# 425543_043_3_2.net
KiCad netlist of a schematic drawn in Altium Designer
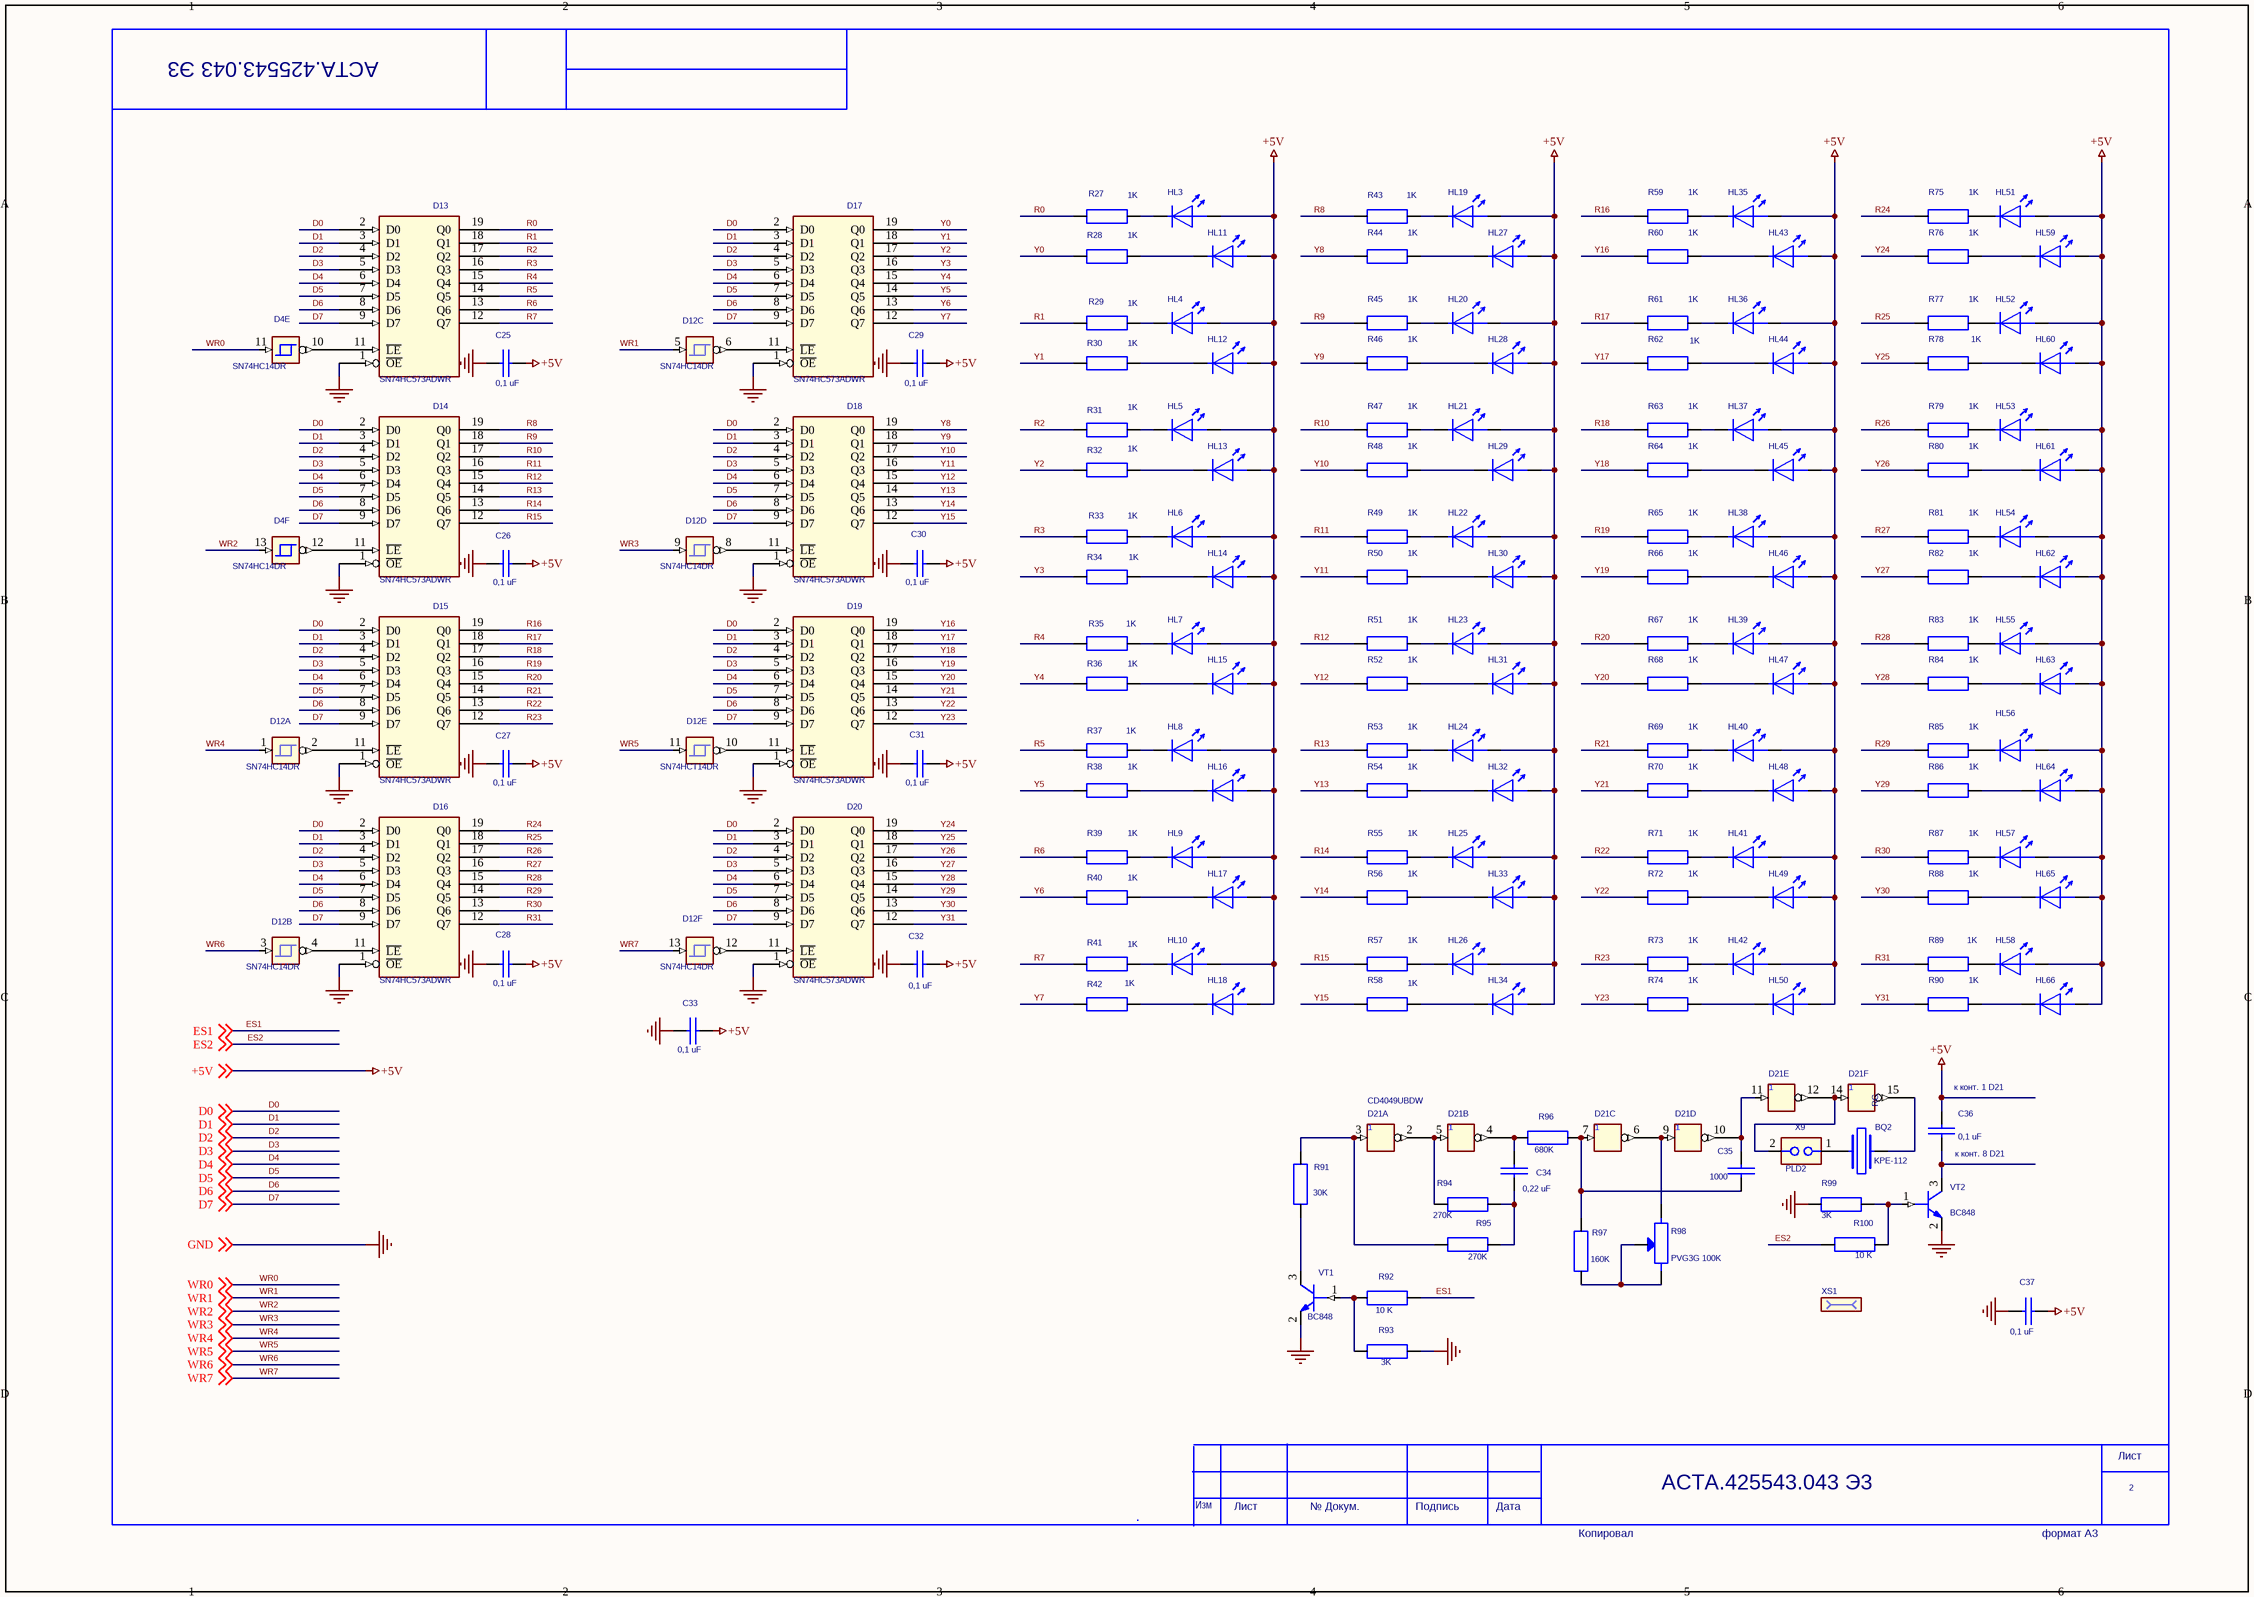
[diagram p0: АСТА.425543.043 Э3 Лист2.SchDoc]

(export (version "E")
  (design (tool "Eeschema 10.0.6"))
  (components
    (comp (ref "BQ2")
      (value "KPE-112")
      (fields (field (name "TYP") "RG"))
      (libsource (lib "*") (part "QUARTZ"))
    )
    (comp (ref "C25") (value "0,1 uF") (footprint "1206.PRT") (libsource (lib "*") (part "CHIP-C")))
    (comp (ref "C26") (value "0,1 uF") (footprint "1206.PRT") (libsource (lib "*") (part "CHIP-C")))
    (comp (ref "C27") (value "0,1 uF") (footprint "1206.PRT") (libsource (lib "*") (part "CHIP-C")))
    (comp (ref "C28") (value "0,1 uF") (footprint "1206.PRT") (libsource (lib "*") (part "CHIP-C")))
    (comp (ref "C29") (value "0,1 uF") (footprint "1206.PRT") (libsource (lib "*") (part "CHIP-C")))
    (comp (ref "C30") (value "0,1 uF") (footprint "1206.PRT") (libsource (lib "*") (part "CHIP-C")))
    (comp (ref "C31") (value "0,1 uF") (footprint "1206.PRT") (libsource (lib "*") (part "CHIP-C")))
    (comp (ref "C32") (value "0,1 uF") (footprint "1206.PRT") (libsource (lib "*") (part "CHIP-C")))
    (comp (ref "C33") (value "0,1 uF") (footprint "1206.PRT") (libsource (lib "*") (part "CHIP-C")))
    (comp (ref "C34") (value "0,22 uF") (footprint "1206.PRT") (libsource (lib "*") (part "CHIP-C")))
    (comp (ref "C35") (value "1000") (footprint "1206.PRT") (libsource (lib "*") (part "CHIP-C")))
    (comp (ref "C36") (value "0,1 uF") (footprint "1206.PRT") (libsource (lib "*") (part "CHIP-C")))
    (comp (ref "C37") (value "0,1 uF") (footprint "1206.PRT") (libsource (lib "*") (part "CHIP-C")))
    (comp (ref "D4") (value "SN74HC14DR") (libsource (lib "*") (part "14069_5")))
    (comp (ref "D12") (value "SN74HC14DR") (libsource (lib "*") (part "74HC14_1")))
    (comp (ref "D13") (value "SN74HC573ADWR") (libsource (lib "*") (part "74HC573_0")))
    (comp (ref "D14") (value "SN74HC573ADWR") (libsource (lib "*") (part "74HC573_5")))
    (comp (ref "D15") (value "SN74HC573ADWR") (libsource (lib "*") (part "74HC573_0")))
    (comp (ref "D16") (value "SN74HC573ADWR") (libsource (lib "*") (part "74HC573_0")))
    (comp (ref "D17") (value "SN74HC573ADWR") (libsource (lib "*") (part "74HC573_6")))
    (comp (ref "D18") (value "SN74HC573ADWR") (libsource (lib "*") (part "74HC573_0")))
    (comp (ref "D19") (value "SN74HC573ADWR") (libsource (lib "*") (part "74HC573_0")))
    (comp (ref "D20") (value "SN74HC573ADWR") (libsource (lib "*") (part "74HC573_0")))
    (comp (ref "D21") (value "CD4049UBDW") (libsource (lib "*") (part "4049_0")))
    (comp (ref "HL3") (value "L-934ID-5V") (libsource (lib "*") (part "AL307AM")))
    (comp (ref "HL4") (value "L-934ID-5V") (libsource (lib "*") (part "AL307AM")))
    (comp (ref "HL5") (value "L-934ID-5V") (libsource (lib "*") (part "AL307AM")))
    (comp (ref "HL6") (value "L-934ID-5V") (libsource (lib "*") (part "AL307AM")))
    (comp (ref "HL7") (value "L-934ID-5V") (libsource (lib "*") (part "AL307AM")))
    (comp (ref "HL8") (value "L-934ID-5V") (libsource (lib "*") (part "AL307AM")))
    (comp (ref "HL9") (value "L-934ID-5V") (libsource (lib "*") (part "AL307AM")))
    (comp (ref "HL10") (value "L-934ID-5V") (libsource (lib "*") (part "AL307AM")))
    (comp (ref "HL11") (value "L-934YD-5V") (libsource (lib "*") (part "AL307AM")))
    (comp (ref "HL12") (value "L-934YD-5V") (libsource (lib "*") (part "AL307AM")))
    (comp (ref "HL13") (value "L-934YD-5V") (libsource (lib "*") (part "AL307AM")))
    (comp (ref "HL14") (value "L-934YD-5V") (libsource (lib "*") (part "AL307AM")))
    (comp (ref "HL15") (value "L-934YD-5V") (libsource (lib "*") (part "AL307AM")))
    (comp (ref "HL16") (value "L-934YD-5V") (libsource (lib "*") (part "AL307AM")))
    (comp (ref "HL17") (value "L-934YD-5V") (libsource (lib "*") (part "AL307AM")))
    (comp (ref "HL18") (value "L-934YD-5V") (libsource (lib "*") (part "AL307AM")))
    (comp (ref "HL19") (value "L-934ID-5V") (libsource (lib "*") (part "AL307AM")))
    (comp (ref "HL20") (value "L-934ID-5V") (libsource (lib "*") (part "AL307AM")))
    (comp (ref "HL21") (value "L-934ID-5V") (libsource (lib "*") (part "AL307AM")))
    (comp (ref "HL22") (value "L-934ID-5V") (libsource (lib "*") (part "AL307AM")))
    (comp (ref "HL23") (value "L-934ID-5V") (libsource (lib "*") (part "AL307AM")))
    (comp (ref "HL24") (value "L-934ID-5V") (libsource (lib "*") (part "AL307AM")))
    (comp (ref "HL25") (value "L-934ID-5V") (libsource (lib "*") (part "AL307AM")))
    (comp (ref "HL26") (value "L-934ID-5V") (libsource (lib "*") (part "AL307AM")))
    (comp (ref "HL27") (value "L-934YD-5V") (libsource (lib "*") (part "AL307AM")))
    (comp (ref "HL28") (value "L-934YD-5V") (libsource (lib "*") (part "AL307AM")))
    (comp (ref "HL29") (value "L-934YD-5V") (libsource (lib "*") (part "AL307AM")))
    (comp (ref "HL30") (value "L-934YD-5V") (libsource (lib "*") (part "AL307AM")))
    (comp (ref "HL31") (value "L-934YD-5V") (libsource (lib "*") (part "AL307AM")))
    (comp (ref "HL32") (value "L-934YD-5V") (libsource (lib "*") (part "AL307AM")))
    (comp (ref "HL33") (value "L-934YD-5V") (libsource (lib "*") (part "AL307AM")))
    (comp (ref "HL34") (value "L-934YD-5V") (libsource (lib "*") (part "AL307AM")))
    (comp (ref "HL35") (value "L-934ID-5V") (libsource (lib "*") (part "AL307AM")))
    (comp (ref "HL36") (value "L-934ID-5V") (libsource (lib "*") (part "AL307AM")))
    (comp (ref "HL37") (value "L-934ID-5V") (libsource (lib "*") (part "AL307AM")))
    (comp (ref "HL38") (value "L-934ID-5V") (libsource (lib "*") (part "AL307AM")))
    (comp (ref "HL39") (value "L-934ID-5V") (libsource (lib "*") (part "AL307AM")))
    (comp (ref "HL40") (value "L-934ID-5V") (libsource (lib "*") (part "AL307AM")))
    (comp (ref "HL41") (value "L-934ID-5V") (libsource (lib "*") (part "AL307AM")))
    (comp (ref "HL42") (value "L-934ID-5V") (libsource (lib "*") (part "AL307AM")))
    (comp (ref "HL43") (value "L-934YD-5V") (libsource (lib "*") (part "AL307AM")))
    (comp (ref "HL44") (value "L-934YD-5V") (libsource (lib "*") (part "AL307AM")))
    (comp (ref "HL45") (value "L-934YD-5V") (libsource (lib "*") (part "AL307AM")))
    (comp (ref "HL46") (value "L-934YD-5V") (libsource (lib "*") (part "AL307AM")))
    (comp (ref "HL47") (value "L-934YD-5V") (libsource (lib "*") (part "AL307AM")))
    (comp (ref "HL48") (value "L-934YD-5V") (libsource (lib "*") (part "AL307AM")))
    (comp (ref "HL49") (value "L-934YD-5V") (libsource (lib "*") (part "AL307AM")))
    (comp (ref "HL50") (value "L-934YD-5V") (libsource (lib "*") (part "AL307AM")))
    (comp (ref "HL51") (value "L-934ID-5V") (libsource (lib "*") (part "AL307AM")))
    (comp (ref "HL52") (value "L-934YD-5V") (libsource (lib "*") (part "AL307AM")))
    (comp (ref "HL53") (value "L-934ID-5V") (libsource (lib "*") (part "AL307AM")))
    (comp (ref "HL54") (value "L-934ID-5V") (libsource (lib "*") (part "AL307AM")))
    (comp (ref "HL55") (value "L-934ID-5V") (libsource (lib "*") (part "AL307AM")))
    (comp (ref "HL56") (value "L-934ID-5V") (libsource (lib "*") (part "AL307AM")))
    (comp (ref "HL57") (value "L-934ID-5V") (libsource (lib "*") (part "AL307AM")))
    (comp (ref "HL58") (value "L-934ID-5V") (libsource (lib "*") (part "AL307AM")))
    (comp (ref "HL59") (value "L-934ID-5V") (libsource (lib "*") (part "AL307AM")))
    (comp (ref "HL60") (value "L-934YD-5V") (libsource (lib "*") (part "AL307AM")))
    (comp (ref "HL61") (value "L-934YD-5V") (libsource (lib "*") (part "AL307AM")))
    (comp (ref "HL62") (value "L-934YD-5V") (libsource (lib "*") (part "AL307AM")))
    (comp (ref "HL63") (value "L-934YD-5V") (libsource (lib "*") (part "AL307AM")))
    (comp (ref "HL64") (value "L-934YD-5V") (libsource (lib "*") (part "AL307AM")))
    (comp (ref "HL65") (value "L-934YD-5V") (libsource (lib "*") (part "AL307AM")))
    (comp (ref "HL66") (value "L-934YD-5V") (libsource (lib "*") (part "AL307AM")))
    (comp (ref "R27") (value "1K") (footprint "1206.PRT") (libsource (lib "*") (part "CHIP-R")))
    (comp (ref "R28") (value "1K") (footprint "1206.PRT") (libsource (lib "*") (part "CHIP-R")))
    (comp (ref "R29") (value "1K") (footprint "1206.PRT") (libsource (lib "*") (part "CHIP-R")))
    (comp (ref "R30") (value "1K") (footprint "1206.PRT") (libsource (lib "*") (part "CHIP-R")))
    (comp (ref "R31") (value "1K") (footprint "1206.PRT") (libsource (lib "*") (part "CHIP-R")))
    (comp (ref "R32") (value "1K") (footprint "1206.PRT") (libsource (lib "*") (part "CHIP-R")))
    (comp (ref "R33") (value "1K") (footprint "1206.PRT") (libsource (lib "*") (part "CHIP-R")))
    (comp (ref "R34") (value "1K") (footprint "1206.PRT") (libsource (lib "*") (part "CHIP-R")))
    (comp (ref "R35") (value "1K") (footprint "1206.PRT") (libsource (lib "*") (part "CHIP-R")))
    (comp (ref "R36") (value "1K") (footprint "1206.PRT") (libsource (lib "*") (part "CHIP-R")))
    (comp (ref "R37") (value "1K") (footprint "1206.PRT") (libsource (lib "*") (part "CHIP-R")))
    (comp (ref "R38") (value "1K") (footprint "1206.PRT") (libsource (lib "*") (part "CHIP-R")))
    (comp (ref "R39") (value "1K") (footprint "1206.PRT") (libsource (lib "*") (part "CHIP-R")))
    (comp (ref "R40") (value "1K") (footprint "1206.PRT") (libsource (lib "*") (part "CHIP-R")))
    (comp (ref "R41") (value "1K") (footprint "1206.PRT") (libsource (lib "*") (part "CHIP-R")))
    (comp (ref "R42") (value "1K") (footprint "1206.PRT") (libsource (lib "*") (part "CHIP-R")))
    (comp (ref "R43") (value "1K") (footprint "1206.PRT") (libsource (lib "*") (part "CHIP-R")))
    (comp (ref "R44") (value "1K") (footprint "1206.PRT") (libsource (lib "*") (part "CHIP-R")))
    (comp (ref "R45") (value "1K") (footprint "1206.PRT") (libsource (lib "*") (part "CHIP-R")))
    (comp (ref "R46") (value "1K") (footprint "1206.PRT") (libsource (lib "*") (part "CHIP-R")))
    (comp (ref "R47") (value "1K") (footprint "1206.PRT") (libsource (lib "*") (part "CHIP-R")))
    (comp (ref "R48") (value "1K") (footprint "1206.PRT") (libsource (lib "*") (part "CHIP-R")))
    (comp (ref "R49") (value "1K") (footprint "1206.PRT") (libsource (lib "*") (part "CHIP-R")))
    (comp (ref "R50") (value "1K") (footprint "1206.PRT") (libsource (lib "*") (part "CHIP-R")))
    (comp (ref "R51") (value "1K") (footprint "1206.PRT") (libsource (lib "*") (part "CHIP-R")))
    (comp (ref "R52") (value "1K") (footprint "1206.PRT") (libsource (lib "*") (part "CHIP-R")))
    (comp (ref "R53") (value "1K") (footprint "1206.PRT") (libsource (lib "*") (part "CHIP-R")))
    (comp (ref "R54") (value "1K") (footprint "1206.PRT") (libsource (lib "*") (part "CHIP-R")))
    (comp (ref "R55") (value "1K") (footprint "1206.PRT") (libsource (lib "*") (part "CHIP-R")))
    (comp (ref "R56") (value "1K") (footprint "1206.PRT") (libsource (lib "*") (part "CHIP-R")))
    (comp (ref "R57") (value "1K") (footprint "1206.PRT") (libsource (lib "*") (part "CHIP-R")))
    (comp (ref "R58") (value "1K") (footprint "1206.PRT") (libsource (lib "*") (part "CHIP-R")))
    (comp (ref "R59") (value "1K") (footprint "1206.PRT") (libsource (lib "*") (part "CHIP-R")))
    (comp (ref "R60") (value "1K") (footprint "1206.PRT") (libsource (lib "*") (part "CHIP-R")))
    (comp (ref "R61") (value "1K") (footprint "1206.PRT") (libsource (lib "*") (part "CHIP-R")))
    (comp (ref "R62") (value "1K") (footprint "1206.PRT") (libsource (lib "*") (part "CHIP-R")))
    (comp (ref "R63") (value "1K") (footprint "1206.PRT") (libsource (lib "*") (part "CHIP-R")))
    (comp (ref "R64") (value "1K") (footprint "1206.PRT") (libsource (lib "*") (part "CHIP-R")))
    (comp (ref "R65") (value "1K") (footprint "1206.PRT") (libsource (lib "*") (part "CHIP-R")))
    (comp (ref "R66") (value "1K") (footprint "1206.PRT") (libsource (lib "*") (part "CHIP-R")))
    (comp (ref "R67") (value "1K") (footprint "1206.PRT") (libsource (lib "*") (part "CHIP-R")))
    (comp (ref "R68") (value "1K") (footprint "1206.PRT") (libsource (lib "*") (part "CHIP-R")))
    (comp (ref "R69") (value "1K") (footprint "1206.PRT") (libsource (lib "*") (part "CHIP-R")))
    (comp (ref "R70") (value "1K") (footprint "1206.PRT") (libsource (lib "*") (part "CHIP-R")))
    (comp (ref "R71") (value "1K") (footprint "1206.PRT") (libsource (lib "*") (part "CHIP-R")))
    (comp (ref "R72") (value "1K") (footprint "1206.PRT") (libsource (lib "*") (part "CHIP-R")))
    (comp (ref "R73") (value "1K") (footprint "1206.PRT") (libsource (lib "*") (part "CHIP-R")))
    (comp (ref "R74") (value "1K") (footprint "1206.PRT") (libsource (lib "*") (part "CHIP-R")))
    (comp (ref "R75") (value "1K") (footprint "1206.PRT") (libsource (lib "*") (part "CHIP-R")))
    (comp (ref "R76") (value "1K") (footprint "1206.PRT") (libsource (lib "*") (part "CHIP-R")))
    (comp (ref "R77") (value "1K") (footprint "1206.PRT") (libsource (lib "*") (part "CHIP-R")))
    (comp (ref "R78") (value "1K") (footprint "1206.PRT") (libsource (lib "*") (part "CHIP-R")))
    (comp (ref "R79") (value "1K") (footprint "1206.PRT") (libsource (lib "*") (part "CHIP-R")))
    (comp (ref "R80") (value "1K") (footprint "1206.PRT") (libsource (lib "*") (part "CHIP-R")))
    (comp (ref "R81") (value "1K") (footprint "1206.PRT") (libsource (lib "*") (part "CHIP-R")))
    (comp (ref "R82") (value "1K") (footprint "1206.PRT") (libsource (lib "*") (part "CHIP-R")))
    (comp (ref "R83") (value "1K") (footprint "1206.PRT") (libsource (lib "*") (part "CHIP-R")))
    (comp (ref "R84") (value "1K") (footprint "1206.PRT") (libsource (lib "*") (part "CHIP-R")))
    (comp (ref "R85") (value "1K") (footprint "1206.PRT") (libsource (lib "*") (part "CHIP-R")))
    (comp (ref "R86") (value "1K") (footprint "1206.PRT") (libsource (lib "*") (part "CHIP-R")))
    (comp (ref "R87") (value "1K") (footprint "1206.PRT") (libsource (lib "*") (part "CHIP-R")))
    (comp (ref "R88") (value "1K") (footprint "1206.PRT") (libsource (lib "*") (part "CHIP-R")))
    (comp (ref "R89") (value "1K") (footprint "1206.PRT") (libsource (lib "*") (part "CHIP-R")))
    (comp (ref "R90") (value "1K") (footprint "1206.PRT") (libsource (lib "*") (part "CHIP-R")))
    (comp (ref "R91") (value "30K") (footprint "1206.PRT") (libsource (lib "*") (part "CHIP-R")))
    (comp (ref "R92") (value "10 K") (footprint "1206.PRT") (libsource (lib "*") (part "CHIP-R")))
    (comp (ref "R93") (value "3K") (footprint "1206.PRT") (libsource (lib "*") (part "CHIP-R")))
    (comp (ref "R94") (value "270K") (footprint "1206.PRT") (libsource (lib "*") (part "CHIP-R")))
    (comp (ref "R95") (value "270K") (footprint "1206.PRT") (libsource (lib "*") (part "CHIP-R")))
    (comp (ref "R96") (value "680K") (footprint "1206.PRT") (libsource (lib "*") (part "CHIP-R")))
    (comp (ref "R97") (value "160K") (footprint "1206.PRT") (libsource (lib "*") (part "CHIP-R")))
    (comp (ref "R98") (value "PVG3G 100K") (libsource (lib "*") (part "RESISTOR VAR_1")))
    (comp (ref "R99") (value "3K") (footprint "1206.PRT") (libsource (lib "*") (part "CHIP-R")))
    (comp (ref "R100") (value "10 K") (footprint "1206.PRT") (libsource (lib "*") (part "CHIP-R")))
    (comp (ref "VT1") (value "BC848") (libsource (lib "*") (part "NPN CBE_0")))
    (comp (ref "VT2") (value "BC848") (libsource (lib "*") (part "NPN CBE_0")))
    (comp (ref "X9") (value "PLD2") (libsource (lib "*") (part "EXTEND_22_Dup1")))
    (comp (ref "XS1") (value "EXTEND_11") (libsource (lib "АСТА.425543.043 Э3_Library") (part "EXTEND_11")))
  )
  (nets
    (net (code "1") (name "+5V") (class "Default")
      (node (ref "C25") (pin "2") (pinfunction "2_2") (pintype "passive"))
      (node (ref "C26") (pin "2") (pinfunction "2_2") (pintype "passive"))
      (node (ref "C27") (pin "2") (pinfunction "2_2") (pintype "passive"))
      (node (ref "C28") (pin "2") (pinfunction "2_2") (pintype "passive"))
      (node (ref "C29") (pin "2") (pinfunction "2_2") (pintype "passive"))
      (node (ref "C30") (pin "2") (pinfunction "2_2") (pintype "passive"))
      (node (ref "C31") (pin "2") (pinfunction "2_2") (pintype "passive"))
      (node (ref "C32") (pin "2") (pinfunction "2_2") (pintype "passive"))
      (node (ref "C33") (pin "2") (pinfunction "2_2") (pintype "passive"))
      (node (ref "C36") (pin "2") (pinfunction "2_2") (pintype "passive"))
      (node (ref "C37") (pin "2") (pinfunction "2_2") (pintype "passive"))
      (node (ref "HL10") (pin "1") (pinfunction "ANODE_1") (pintype "passive"))
      (node (ref "HL11") (pin "1") (pinfunction "ANODE_1") (pintype "passive"))
      (node (ref "HL12") (pin "1") (pinfunction "ANODE_1") (pintype "passive"))
      (node (ref "HL13") (pin "1") (pinfunction "ANODE_1") (pintype "passive"))
      (node (ref "HL14") (pin "1") (pinfunction "ANODE_1") (pintype "passive"))
      (node (ref "HL15") (pin "1") (pinfunction "ANODE_1") (pintype "passive"))
      (node (ref "HL16") (pin "1") (pinfunction "ANODE_1") (pintype "passive"))
      (node (ref "HL17") (pin "1") (pinfunction "ANODE_1") (pintype "passive"))
      (node (ref "HL18") (pin "1") (pinfunction "ANODE_1") (pintype "passive"))
      (node (ref "HL19") (pin "1") (pinfunction "ANODE_1") (pintype "passive"))
      (node (ref "HL20") (pin "1") (pinfunction "ANODE_1") (pintype "passive"))
      (node (ref "HL21") (pin "1") (pinfunction "ANODE_1") (pintype "passive"))
      (node (ref "HL22") (pin "1") (pinfunction "ANODE_1") (pintype "passive"))
      (node (ref "HL23") (pin "1") (pinfunction "ANODE_1") (pintype "passive"))
      (node (ref "HL24") (pin "1") (pinfunction "ANODE_1") (pintype "passive"))
      (node (ref "HL25") (pin "1") (pinfunction "ANODE_1") (pintype "passive"))
      (node (ref "HL26") (pin "1") (pinfunction "ANODE_1") (pintype "passive"))
      (node (ref "HL27") (pin "1") (pinfunction "ANODE_1") (pintype "passive"))
      (node (ref "HL28") (pin "1") (pinfunction "ANODE_1") (pintype "passive"))
      (node (ref "HL29") (pin "1") (pinfunction "ANODE_1") (pintype "passive"))
      (node (ref "HL3") (pin "1") (pinfunction "ANODE_1") (pintype "passive"))
      (node (ref "HL30") (pin "1") (pinfunction "ANODE_1") (pintype "passive"))
      (node (ref "HL31") (pin "1") (pinfunction "ANODE_1") (pintype "passive"))
      (node (ref "HL32") (pin "1") (pinfunction "ANODE_1") (pintype "passive"))
      (node (ref "HL33") (pin "1") (pinfunction "ANODE_1") (pintype "passive"))
      (node (ref "HL34") (pin "1") (pinfunction "ANODE_1") (pintype "passive"))
      (node (ref "HL35") (pin "1") (pinfunction "ANODE_1") (pintype "passive"))
      (node (ref "HL36") (pin "1") (pinfunction "ANODE_1") (pintype "passive"))
      (node (ref "HL37") (pin "1") (pinfunction "ANODE_1") (pintype "passive"))
      (node (ref "HL38") (pin "1") (pinfunction "ANODE_1") (pintype "passive"))
      (node (ref "HL39") (pin "1") (pinfunction "ANODE_1") (pintype "passive"))
      (node (ref "HL4") (pin "1") (pinfunction "ANODE_1") (pintype "passive"))
      (node (ref "HL40") (pin "1") (pinfunction "ANODE_1") (pintype "passive"))
      (node (ref "HL41") (pin "1") (pinfunction "ANODE_1") (pintype "passive"))
      (node (ref "HL42") (pin "1") (pinfunction "ANODE_1") (pintype "passive"))
      (node (ref "HL43") (pin "1") (pinfunction "ANODE_1") (pintype "passive"))
      (node (ref "HL44") (pin "1") (pinfunction "ANODE_1") (pintype "passive"))
      (node (ref "HL45") (pin "1") (pinfunction "ANODE_1") (pintype "passive"))
      (node (ref "HL46") (pin "1") (pinfunction "ANODE_1") (pintype "passive"))
      (node (ref "HL47") (pin "1") (pinfunction "ANODE_1") (pintype "passive"))
      (node (ref "HL48") (pin "1") (pinfunction "ANODE_1") (pintype "passive"))
      (node (ref "HL49") (pin "1") (pinfunction "ANODE_1") (pintype "passive"))
      (node (ref "HL5") (pin "1") (pinfunction "ANODE_1") (pintype "passive"))
      (node (ref "HL50") (pin "1") (pinfunction "ANODE_1") (pintype "passive"))
      (node (ref "HL51") (pin "1") (pinfunction "ANODE_1") (pintype "passive"))
      (node (ref "HL52") (pin "1") (pinfunction "ANODE_1") (pintype "passive"))
      (node (ref "HL53") (pin "1") (pinfunction "ANODE_1") (pintype "passive"))
      (node (ref "HL54") (pin "1") (pinfunction "ANODE_1") (pintype "passive"))
      (node (ref "HL55") (pin "1") (pinfunction "ANODE_1") (pintype "passive"))
      (node (ref "HL56") (pin "1") (pinfunction "ANODE_1") (pintype "passive"))
      (node (ref "HL57") (pin "1") (pinfunction "ANODE_1") (pintype "passive"))
      (node (ref "HL58") (pin "1") (pinfunction "ANODE_1") (pintype "passive"))
      (node (ref "HL59") (pin "1") (pinfunction "ANODE_1") (pintype "passive"))
      (node (ref "HL6") (pin "1") (pinfunction "ANODE_1") (pintype "passive"))
      (node (ref "HL60") (pin "1") (pinfunction "ANODE_1") (pintype "passive"))
      (node (ref "HL61") (pin "1") (pinfunction "ANODE_1") (pintype "passive"))
      (node (ref "HL62") (pin "1") (pinfunction "ANODE_1") (pintype "passive"))
      (node (ref "HL63") (pin "1") (pinfunction "ANODE_1") (pintype "passive"))
      (node (ref "HL64") (pin "1") (pinfunction "ANODE_1") (pintype "passive"))
      (node (ref "HL65") (pin "1") (pinfunction "ANODE_1") (pintype "passive"))
      (node (ref "HL66") (pin "1") (pinfunction "ANODE_1") (pintype "passive"))
      (node (ref "HL7") (pin "1") (pinfunction "ANODE_1") (pintype "passive"))
      (node (ref "HL8") (pin "1") (pinfunction "ANODE_1") (pintype "passive"))
      (node (ref "HL9") (pin "1") (pinfunction "ANODE_1") (pintype "passive"))
    )
    (net (code "2") (name "/R0") (class "Default")
      (node (ref "D13") (pin "19") (pinfunction "Q0_19") (pintype "tri_state"))
      (node (ref "R27") (pin "1") (pinfunction "1_1") (pintype "passive"))
    )
    (net (code "3") (name "/R1") (class "Default")
      (node (ref "D13") (pin "18") (pinfunction "Q1_18") (pintype "tri_state"))
      (node (ref "R29") (pin "1") (pinfunction "1_1") (pintype "passive"))
    )
    (net (code "4") (name "/R2") (class "Default")
      (node (ref "D13") (pin "17") (pinfunction "Q2_17") (pintype "tri_state"))
      (node (ref "R31") (pin "1") (pinfunction "1_1") (pintype "passive"))
    )
    (net (code "5") (name "/R3") (class "Default")
      (node (ref "D13") (pin "16") (pinfunction "Q3_16") (pintype "tri_state"))
      (node (ref "R33") (pin "1") (pinfunction "1_1") (pintype "passive"))
    )
    (net (code "6") (name "/R4") (class "Default")
      (node (ref "D13") (pin "15") (pinfunction "Q4_15") (pintype "tri_state"))
      (node (ref "R35") (pin "1") (pinfunction "1_1") (pintype "passive"))
    )
    (net (code "7") (name "/R5") (class "Default")
      (node (ref "D13") (pin "14") (pinfunction "Q5_14") (pintype "tri_state"))
      (node (ref "R37") (pin "1") (pinfunction "1_1") (pintype "passive"))
    )
    (net (code "8") (name "/R6") (class "Default")
      (node (ref "D13") (pin "13") (pinfunction "Q6_13") (pintype "tri_state"))
      (node (ref "R39") (pin "1") (pinfunction "1_1") (pintype "passive"))
    )
    (net (code "9") (name "/R7") (class "Default")
      (node (ref "D13") (pin "12") (pinfunction "Q7_12") (pintype "tri_state"))
      (node (ref "R41") (pin "1") (pinfunction "1_1") (pintype "passive"))
    )
    (net (code "10") (name "/R8") (class "Default")
      (node (ref "D14") (pin "19") (pinfunction "Q0_19") (pintype "tri_state"))
      (node (ref "R43") (pin "1") (pinfunction "1_1") (pintype "passive"))
    )
    (net (code "11") (name "/R9") (class "Default")
      (node (ref "D14") (pin "18") (pinfunction "Q1_18") (pintype "tri_state"))
      (node (ref "R45") (pin "1") (pinfunction "1_1") (pintype "passive"))
    )
    (net (code "12") (name "/R10") (class "Default")
      (node (ref "D14") (pin "17") (pinfunction "Q2_17") (pintype "tri_state"))
      (node (ref "R47") (pin "1") (pinfunction "1_1") (pintype "passive"))
    )
    (net (code "13") (name "/R11") (class "Default")
      (node (ref "D14") (pin "16") (pinfunction "Q3_16") (pintype "tri_state"))
      (node (ref "R49") (pin "1") (pinfunction "1_1") (pintype "passive"))
    )
    (net (code "14") (name "/R12") (class "Default")
      (node (ref "D14") (pin "15") (pinfunction "Q4_15") (pintype "tri_state"))
      (node (ref "R51") (pin "1") (pinfunction "1_1") (pintype "passive"))
    )
    (net (code "15") (name "/R13") (class "Default")
      (node (ref "D14") (pin "14") (pinfunction "Q5_14") (pintype "tri_state"))
      (node (ref "R53") (pin "1") (pinfunction "1_1") (pintype "passive"))
    )
    (net (code "16") (name "/R14") (class "Default")
      (node (ref "D14") (pin "13") (pinfunction "Q6_13") (pintype "tri_state"))
      (node (ref "R55") (pin "1") (pinfunction "1_1") (pintype "passive"))
    )
    (net (code "17") (name "/R15") (class "Default")
      (node (ref "D14") (pin "12") (pinfunction "Q7_12") (pintype "tri_state"))
      (node (ref "R57") (pin "1") (pinfunction "1_1") (pintype "passive"))
    )
    (net (code "18") (name "/R16") (class "Default")
      (node (ref "D15") (pin "19") (pinfunction "Q0_19") (pintype "tri_state"))
      (node (ref "R59") (pin "1") (pinfunction "1_1") (pintype "passive"))
    )
    (net (code "19") (name "/R17") (class "Default")
      (node (ref "D15") (pin "18") (pinfunction "Q1_18") (pintype "tri_state"))
      (node (ref "R61") (pin "1") (pinfunction "1_1") (pintype "passive"))
    )
    (net (code "20") (name "/R18") (class "Default")
      (node (ref "D15") (pin "17") (pinfunction "Q2_17") (pintype "tri_state"))
      (node (ref "R63") (pin "1") (pinfunction "1_1") (pintype "passive"))
    )
    (net (code "21") (name "/R19") (class "Default")
      (node (ref "D15") (pin "16") (pinfunction "Q3_16") (pintype "tri_state"))
      (node (ref "R65") (pin "1") (pinfunction "1_1") (pintype "passive"))
    )
    (net (code "22") (name "/R20") (class "Default")
      (node (ref "D15") (pin "15") (pinfunction "Q4_15") (pintype "tri_state"))
      (node (ref "R67") (pin "1") (pinfunction "1_1") (pintype "passive"))
    )
    (net (code "23") (name "/R21") (class "Default")
      (node (ref "D15") (pin "14") (pinfunction "Q5_14") (pintype "tri_state"))
      (node (ref "R69") (pin "1") (pinfunction "1_1") (pintype "passive"))
    )
    (net (code "24") (name "/R22") (class "Default")
      (node (ref "D15") (pin "13") (pinfunction "Q6_13") (pintype "tri_state"))
      (node (ref "R71") (pin "1") (pinfunction "1_1") (pintype "passive"))
    )
    (net (code "25") (name "/R23") (class "Default")
      (node (ref "D15") (pin "12") (pinfunction "Q7_12") (pintype "tri_state"))
      (node (ref "R73") (pin "1") (pinfunction "1_1") (pintype "passive"))
    )
    (net (code "26") (name "/R24") (class "Default")
      (node (ref "D16") (pin "19") (pinfunction "Q0_19") (pintype "tri_state"))
      (node (ref "R75") (pin "1") (pinfunction "1_1") (pintype "passive"))
    )
    (net (code "27") (name "/R25") (class "Default")
      (node (ref "D16") (pin "18") (pinfunction "Q1_18") (pintype "tri_state"))
      (node (ref "R77") (pin "1") (pinfunction "1_1") (pintype "passive"))
    )
    (net (code "28") (name "/R26") (class "Default")
      (node (ref "D16") (pin "17") (pinfunction "Q2_17") (pintype "tri_state"))
      (node (ref "R79") (pin "1") (pinfunction "1_1") (pintype "passive"))
    )
    (net (code "29") (name "/R27") (class "Default")
      (node (ref "D16") (pin "16") (pinfunction "Q3_16") (pintype "tri_state"))
      (node (ref "R81") (pin "1") (pinfunction "1_1") (pintype "passive"))
    )
    (net (code "30") (name "/R28") (class "Default")
      (node (ref "D16") (pin "15") (pinfunction "Q4_15") (pintype "tri_state"))
      (node (ref "R83") (pin "1") (pinfunction "1_1") (pintype "passive"))
    )
    (net (code "31") (name "/R29") (class "Default")
      (node (ref "D16") (pin "14") (pinfunction "Q5_14") (pintype "tri_state"))
      (node (ref "R85") (pin "1") (pinfunction "1_1") (pintype "passive"))
    )
    (net (code "32") (name "/R30") (class "Default")
      (node (ref "D16") (pin "13") (pinfunction "Q6_13") (pintype "tri_state"))
      (node (ref "R87") (pin "1") (pinfunction "1_1") (pintype "passive"))
    )
    (net (code "33") (name "/R31") (class "Default")
      (node (ref "D16") (pin "12") (pinfunction "Q7_12") (pintype "tri_state"))
      (node (ref "R89") (pin "1") (pinfunction "1_1") (pintype "passive"))
    )
    (net (code "34") (name "/Y0") (class "Default")
      (node (ref "D17") (pin "19") (pinfunction "Q0_19") (pintype "tri_state"))
      (node (ref "R28") (pin "1") (pinfunction "1_1") (pintype "passive"))
    )
    (net (code "35") (name "/Y1") (class "Default")
      (node (ref "D17") (pin "18") (pinfunction "Q1_18") (pintype "tri_state"))
      (node (ref "R30") (pin "1") (pinfunction "1_1") (pintype "passive"))
    )
    (net (code "36") (name "/Y2") (class "Default")
      (node (ref "D17") (pin "17") (pinfunction "Q2_17") (pintype "tri_state"))
      (node (ref "R32") (pin "1") (pinfunction "1_1") (pintype "passive"))
    )
    (net (code "37") (name "/Y3") (class "Default")
      (node (ref "D17") (pin "16") (pinfunction "Q3_16") (pintype "tri_state"))
      (node (ref "R34") (pin "1") (pinfunction "1_1") (pintype "passive"))
    )
    (net (code "38") (name "/Y4") (class "Default")
      (node (ref "D17") (pin "15") (pinfunction "Q4_15") (pintype "tri_state"))
      (node (ref "R36") (pin "1") (pinfunction "1_1") (pintype "passive"))
    )
    (net (code "39") (name "/Y5") (class "Default")
      (node (ref "D17") (pin "14") (pinfunction "Q5_14") (pintype "tri_state"))
      (node (ref "R38") (pin "1") (pinfunction "1_1") (pintype "passive"))
    )
    (net (code "40") (name "/Y6") (class "Default")
      (node (ref "D17") (pin "13") (pinfunction "Q6_13") (pintype "tri_state"))
      (node (ref "R40") (pin "1") (pinfunction "1_1") (pintype "passive"))
    )
    (net (code "41") (name "/Y7") (class "Default")
      (node (ref "D17") (pin "12") (pinfunction "Q7_12") (pintype "tri_state"))
      (node (ref "R42") (pin "1") (pinfunction "1_1") (pintype "passive"))
    )
    (net (code "42") (name "/Y8") (class "Default")
      (node (ref "D18") (pin "19") (pinfunction "Q0_19") (pintype "tri_state"))
      (node (ref "R44") (pin "1") (pinfunction "1_1") (pintype "passive"))
    )
    (net (code "43") (name "/Y9") (class "Default")
      (node (ref "D18") (pin "18") (pinfunction "Q1_18") (pintype "tri_state"))
      (node (ref "R46") (pin "1") (pinfunction "1_1") (pintype "passive"))
    )
    (net (code "44") (name "/Y10") (class "Default")
      (node (ref "D18") (pin "17") (pinfunction "Q2_17") (pintype "tri_state"))
      (node (ref "R48") (pin "1") (pinfunction "1_1") (pintype "passive"))
    )
    (net (code "45") (name "/Y11") (class "Default")
      (node (ref "D18") (pin "16") (pinfunction "Q3_16") (pintype "tri_state"))
      (node (ref "R50") (pin "1") (pinfunction "1_1") (pintype "passive"))
    )
    (net (code "46") (name "/Y12") (class "Default")
      (node (ref "D18") (pin "15") (pinfunction "Q4_15") (pintype "tri_state"))
      (node (ref "R52") (pin "1") (pinfunction "1_1") (pintype "passive"))
    )
    (net (code "47") (name "/Y13") (class "Default")
      (node (ref "D18") (pin "14") (pinfunction "Q5_14") (pintype "tri_state"))
      (node (ref "R54") (pin "1") (pinfunction "1_1") (pintype "passive"))
    )
    (net (code "48") (name "/Y14") (class "Default")
      (node (ref "D18") (pin "13") (pinfunction "Q6_13") (pintype "tri_state"))
      (node (ref "R56") (pin "1") (pinfunction "1_1") (pintype "passive"))
    )
    (net (code "49") (name "/Y15") (class "Default")
      (node (ref "D18") (pin "12") (pinfunction "Q7_12") (pintype "tri_state"))
      (node (ref "R58") (pin "1") (pinfunction "1_1") (pintype "passive"))
    )
    (net (code "50") (name "/Y16") (class "Default")
      (node (ref "D19") (pin "19") (pinfunction "Q0_19") (pintype "tri_state"))
      (node (ref "R60") (pin "1") (pinfunction "1_1") (pintype "passive"))
    )
    (net (code "51") (name "/Y17") (class "Default")
      (node (ref "D19") (pin "18") (pinfunction "Q1_18") (pintype "tri_state"))
      (node (ref "R62") (pin "1") (pinfunction "1_1") (pintype "passive"))
    )
    (net (code "52") (name "/Y18") (class "Default")
      (node (ref "D19") (pin "17") (pinfunction "Q2_17") (pintype "tri_state"))
      (node (ref "R64") (pin "1") (pinfunction "1_1") (pintype "passive"))
    )
    (net (code "53") (name "/Y19") (class "Default")
      (node (ref "D19") (pin "16") (pinfunction "Q3_16") (pintype "tri_state"))
      (node (ref "R66") (pin "1") (pinfunction "1_1") (pintype "passive"))
    )
    (net (code "54") (name "/Y20") (class "Default")
      (node (ref "D19") (pin "15") (pinfunction "Q4_15") (pintype "tri_state"))
      (node (ref "R68") (pin "1") (pinfunction "1_1") (pintype "passive"))
    )
    (net (code "55") (name "/Y21") (class "Default")
      (node (ref "D19") (pin "14") (pinfunction "Q5_14") (pintype "tri_state"))
      (node (ref "R70") (pin "1") (pinfunction "1_1") (pintype "passive"))
    )
    (net (code "56") (name "/Y22") (class "Default")
      (node (ref "D19") (pin "13") (pinfunction "Q6_13") (pintype "tri_state"))
      (node (ref "R72") (pin "1") (pinfunction "1_1") (pintype "passive"))
    )
    (net (code "57") (name "/Y23") (class "Default")
      (node (ref "D19") (pin "12") (pinfunction "Q7_12") (pintype "tri_state"))
      (node (ref "R74") (pin "1") (pinfunction "1_1") (pintype "passive"))
    )
    (net (code "58") (name "/Y24") (class "Default")
      (node (ref "D20") (pin "19") (pinfunction "Q0_19") (pintype "tri_state"))
      (node (ref "R76") (pin "1") (pinfunction "1_1") (pintype "passive"))
    )
    (net (code "59") (name "/Y25") (class "Default")
      (node (ref "D20") (pin "18") (pinfunction "Q1_18") (pintype "tri_state"))
      (node (ref "R78") (pin "1") (pinfunction "1_1") (pintype "passive"))
    )
    (net (code "60") (name "/Y26") (class "Default")
      (node (ref "D20") (pin "17") (pinfunction "Q2_17") (pintype "tri_state"))
      (node (ref "R80") (pin "1") (pinfunction "1_1") (pintype "passive"))
    )
    (net (code "61") (name "/Y27") (class "Default")
      (node (ref "D20") (pin "16") (pinfunction "Q3_16") (pintype "tri_state"))
      (node (ref "R82") (pin "1") (pinfunction "1_1") (pintype "passive"))
    )
    (net (code "62") (name "/Y28") (class "Default")
      (node (ref "D20") (pin "15") (pinfunction "Q4_15") (pintype "tri_state"))
      (node (ref "R84") (pin "1") (pinfunction "1_1") (pintype "passive"))
    )
    (net (code "63") (name "/Y29") (class "Default")
      (node (ref "D20") (pin "14") (pinfunction "Q5_14") (pintype "tri_state"))
      (node (ref "R86") (pin "1") (pinfunction "1_1") (pintype "passive"))
    )
    (net (code "64") (name "/Y30") (class "Default")
      (node (ref "D20") (pin "13") (pinfunction "Q6_13") (pintype "tri_state"))
      (node (ref "R88") (pin "1") (pinfunction "1_1") (pintype "passive"))
    )
    (net (code "65") (name "/Y31") (class "Default")
      (node (ref "D20") (pin "12") (pinfunction "Q7_12") (pintype "tri_state"))
      (node (ref "R90") (pin "1") (pinfunction "1_1") (pintype "passive"))
    )
    (net (code "66") (name "D0") (class "Default")
      (node (ref "D13") (pin "2") (pinfunction "D0_2") (pintype "input"))
      (node (ref "D14") (pin "2") (pinfunction "D0_2") (pintype "input"))
      (node (ref "D15") (pin "2") (pinfunction "D0_2") (pintype "input"))
      (node (ref "D16") (pin "2") (pinfunction "D0_2") (pintype "input"))
      (node (ref "D17") (pin "2") (pinfunction "D0_2") (pintype "input"))
      (node (ref "D18") (pin "2") (pinfunction "D0_2") (pintype "input"))
      (node (ref "D19") (pin "2") (pinfunction "D0_2") (pintype "input"))
      (node (ref "D20") (pin "2") (pinfunction "D0_2") (pintype "input"))
    )
    (net (code "67") (name "D1") (class "Default")
      (node (ref "D13") (pin "3") (pinfunction "D1_3") (pintype "input"))
      (node (ref "D14") (pin "3") (pinfunction "D1_3") (pintype "input"))
      (node (ref "D15") (pin "3") (pinfunction "D1_3") (pintype "input"))
      (node (ref "D16") (pin "3") (pinfunction "D1_3") (pintype "input"))
      (node (ref "D17") (pin "3") (pinfunction "D1_3") (pintype "input"))
      (node (ref "D18") (pin "3") (pinfunction "D1_3") (pintype "input"))
      (node (ref "D19") (pin "3") (pinfunction "D1_3") (pintype "input"))
      (node (ref "D20") (pin "3") (pinfunction "D1_3") (pintype "input"))
    )
    (net (code "68") (name "D2") (class "Default")
      (node (ref "D13") (pin "4") (pinfunction "D2_4") (pintype "input"))
      (node (ref "D14") (pin "4") (pinfunction "D2_4") (pintype "input"))
      (node (ref "D15") (pin "4") (pinfunction "D2_4") (pintype "input"))
      (node (ref "D16") (pin "4") (pinfunction "D2_4") (pintype "input"))
      (node (ref "D17") (pin "4") (pinfunction "D2_4") (pintype "input"))
      (node (ref "D18") (pin "4") (pinfunction "D2_4") (pintype "input"))
      (node (ref "D19") (pin "4") (pinfunction "D2_4") (pintype "input"))
      (node (ref "D20") (pin "4") (pinfunction "D2_4") (pintype "input"))
    )
    (net (code "69") (name "D3") (class "Default")
      (node (ref "D13") (pin "5") (pinfunction "D3_5") (pintype "input"))
      (node (ref "D14") (pin "5") (pinfunction "D3_5") (pintype "input"))
      (node (ref "D15") (pin "5") (pinfunction "D3_5") (pintype "input"))
      (node (ref "D16") (pin "5") (pinfunction "D3_5") (pintype "input"))
      (node (ref "D17") (pin "5") (pinfunction "D3_5") (pintype "input"))
      (node (ref "D18") (pin "5") (pinfunction "D3_5") (pintype "input"))
      (node (ref "D19") (pin "5") (pinfunction "D3_5") (pintype "input"))
      (node (ref "D20") (pin "5") (pinfunction "D3_5") (pintype "input"))
    )
    (net (code "70") (name "D4") (class "Default")
      (node (ref "D13") (pin "6") (pinfunction "D4_6") (pintype "input"))
      (node (ref "D14") (pin "6") (pinfunction "D4_6") (pintype "input"))
      (node (ref "D15") (pin "6") (pinfunction "D4_6") (pintype "input"))
      (node (ref "D16") (pin "6") (pinfunction "D4_6") (pintype "input"))
      (node (ref "D17") (pin "6") (pinfunction "D4_6") (pintype "input"))
      (node (ref "D18") (pin "6") (pinfunction "D4_6") (pintype "input"))
      (node (ref "D19") (pin "6") (pinfunction "D4_6") (pintype "input"))
      (node (ref "D20") (pin "6") (pinfunction "D4_6") (pintype "input"))
    )
    (net (code "71") (name "D5") (class "Default")
      (node (ref "D13") (pin "7") (pinfunction "D5_7") (pintype "input"))
      (node (ref "D14") (pin "7") (pinfunction "D5_7") (pintype "input"))
      (node (ref "D15") (pin "7") (pinfunction "D5_7") (pintype "input"))
      (node (ref "D16") (pin "7") (pinfunction "D5_7") (pintype "input"))
      (node (ref "D17") (pin "7") (pinfunction "D5_7") (pintype "input"))
      (node (ref "D18") (pin "7") (pinfunction "D5_7") (pintype "input"))
      (node (ref "D19") (pin "7") (pinfunction "D5_7") (pintype "input"))
      (node (ref "D20") (pin "7") (pinfunction "D5_7") (pintype "input"))
    )
    (net (code "72") (name "D6") (class "Default")
      (node (ref "D13") (pin "8") (pinfunction "D6_8") (pintype "input"))
      (node (ref "D14") (pin "8") (pinfunction "D6_8") (pintype "input"))
      (node (ref "D15") (pin "8") (pinfunction "D6_8") (pintype "input"))
      (node (ref "D16") (pin "8") (pinfunction "D6_8") (pintype "input"))
      (node (ref "D17") (pin "8") (pinfunction "D6_8") (pintype "input"))
      (node (ref "D18") (pin "8") (pinfunction "D6_8") (pintype "input"))
      (node (ref "D19") (pin "8") (pinfunction "D6_8") (pintype "input"))
      (node (ref "D20") (pin "8") (pinfunction "D6_8") (pintype "input"))
    )
    (net (code "73") (name "D7") (class "Default")
      (node (ref "D13") (pin "9") (pinfunction "D7_9") (pintype "input"))
      (node (ref "D14") (pin "9") (pinfunction "D7_9") (pintype "input"))
      (node (ref "D15") (pin "9") (pinfunction "D7_9") (pintype "input"))
      (node (ref "D16") (pin "9") (pinfunction "D7_9") (pintype "input"))
      (node (ref "D17") (pin "9") (pinfunction "D7_9") (pintype "input"))
      (node (ref "D18") (pin "9") (pinfunction "D7_9") (pintype "input"))
      (node (ref "D19") (pin "9") (pinfunction "D7_9") (pintype "input"))
      (node (ref "D20") (pin "9") (pinfunction "D7_9") (pintype "input"))
    )
    (net (code "74") (name "ES1") (class "Default")
      (node (ref "R92") (pin "1") (pinfunction "1_1") (pintype "passive"))
    )
    (net (code "75") (name "ES2") (class "Default")
      (node (ref "R100") (pin "2") (pinfunction "2_2") (pintype "passive"))
    )
    (net (code "76") (name "GND") (class "Default")
      (node (ref "C25") (pin "1") (pinfunction "1_1") (pintype "passive"))
      (node (ref "C26") (pin "1") (pinfunction "1_1") (pintype "passive"))
      (node (ref "C27") (pin "1") (pinfunction "1_1") (pintype "passive"))
      (node (ref "C28") (pin "1") (pinfunction "1_1") (pintype "passive"))
      (node (ref "C29") (pin "1") (pinfunction "1_1") (pintype "passive"))
      (node (ref "C30") (pin "1") (pinfunction "1_1") (pintype "passive"))
      (node (ref "C31") (pin "1") (pinfunction "1_1") (pintype "passive"))
      (node (ref "C32") (pin "1") (pinfunction "1_1") (pintype "passive"))
      (node (ref "C33") (pin "1") (pinfunction "1_1") (pintype "passive"))
      (node (ref "C37") (pin "1") (pinfunction "1_1") (pintype "passive"))
      (node (ref "D12") (pin "7") (pinfunction "GND_7") (pintype "power_in"))
      (node (ref "D13") (pin "1") (pinfunction "~{OE}_1") (pintype "input"))
      (node (ref "D13") (pin "10") (pinfunction "GND_10") (pintype "power_in"))
      (node (ref "D14") (pin "1") (pinfunction "~{OE}_1") (pintype "input"))
      (node (ref "D14") (pin "10") (pinfunction "GND_10") (pintype "power_in"))
      (node (ref "D15") (pin "1") (pinfunction "~{OE}_1") (pintype "input"))
      (node (ref "D15") (pin "10") (pinfunction "GND_10") (pintype "power_in"))
      (node (ref "D16") (pin "1") (pinfunction "~{OE}_1") (pintype "input"))
      (node (ref "D16") (pin "10") (pinfunction "GND_10") (pintype "power_in"))
      (node (ref "D17") (pin "1") (pinfunction "~{OE}_1") (pintype "input"))
      (node (ref "D17") (pin "10") (pinfunction "GND_10") (pintype "power_in"))
      (node (ref "D18") (pin "1") (pinfunction "~{OE}_1") (pintype "input"))
      (node (ref "D18") (pin "10") (pinfunction "GND_10") (pintype "power_in"))
      (node (ref "D19") (pin "1") (pinfunction "~{OE}_1") (pintype "input"))
      (node (ref "D19") (pin "10") (pinfunction "GND_10") (pintype "power_in"))
      (node (ref "D20") (pin "1") (pinfunction "~{OE}_1") (pintype "input"))
      (node (ref "D20") (pin "10") (pinfunction "GND_10") (pintype "power_in"))
      (node (ref "D4") (pin "GND") (pinfunction "GND_GND") (pintype "power_in"))
      (node (ref "R93") (pin "2") (pinfunction "2_2") (pintype "passive"))
      (node (ref "R99") (pin "1") (pinfunction "1_1") (pintype "passive"))
      (node (ref "VT1") (pin "2") (pinfunction "EMITTER_2") (pintype "passive"))
      (node (ref "VT2") (pin "2") (pinfunction "EMITTER_2") (pintype "passive"))
    )
    (net (code "77") (name "Net-(BQ2-Pad1)") (class "Default")
      (node (ref "BQ2") (pin "1") (pinfunction "1_1") (pintype "passive"))
      (node (ref "X9") (pin "1") (pinfunction "1_1") (pintype "passive"))
    )
    (net (code "78") (name "Net-(C34-Pad1)") (class "Default")
      (node (ref "C34") (pin "1") (pinfunction "1_1") (pintype "passive"))
      (node (ref "R94") (pin "1") (pinfunction "1_1") (pintype "passive"))
      (node (ref "R95") (pin "1") (pinfunction "1_1") (pintype "passive"))
    )
    (net (code "79") (name "Net-(D12A-Y)") (class "Default")
      (node (ref "D12") (pin "2") (pinfunction "Y_2") (pintype "output"))
      (node (ref "D15") (pin "11") (pinfunction "~{LE}_11") (pintype "input"))
    )
    (net (code "80") (name "Net-(D12B-Y)") (class "Default")
      (node (ref "D12") (pin "4") (pinfunction "Y_4") (pintype "output"))
      (node (ref "D16") (pin "11") (pinfunction "~{LE}_11") (pintype "input"))
    )
    (net (code "81") (name "Net-(D12C-Y)") (class "Default")
      (node (ref "D12") (pin "6") (pinfunction "Y_6") (pintype "output"))
      (node (ref "D17") (pin "11") (pinfunction "~{LE}_11") (pintype "input"))
    )
    (net (code "82") (name "Net-(D12D-Y)") (class "Default")
      (node (ref "D12") (pin "8") (pinfunction "Y_8") (pintype "output"))
      (node (ref "D18") (pin "11") (pinfunction "~{LE}_11") (pintype "input"))
    )
    (net (code "83") (name "Net-(D12E-Y)") (class "Default")
      (node (ref "D12") (pin "10") (pinfunction "Y_10") (pintype "output"))
      (node (ref "D19") (pin "11") (pinfunction "~{LE}_11") (pintype "input"))
    )
    (net (code "84") (name "Net-(D12F-Y)") (class "Default")
      (node (ref "D12") (pin "12") (pinfunction "Y_12") (pintype "output"))
      (node (ref "D20") (pin "11") (pinfunction "~{LE}_11") (pintype "input"))
    )
    (net (code "85") (name "Net-(D13-~{LE})") (class "Default")
      (node (ref "D13") (pin "11") (pinfunction "~{LE}_11") (pintype "input"))
      (node (ref "D4") (pin "10") (pinfunction "O_10") (pintype "output"))
    )
    (net (code "86") (name "Net-(D14-~{LE})") (class "Default")
      (node (ref "D14") (pin "11") (pinfunction "~{LE}_11") (pintype "input"))
      (node (ref "D4") (pin "12") (pinfunction "O_12") (pintype "output"))
    )
    (net (code "87") (name "Net-(D21A-I)") (class "Default")
      (node (ref "D21") (pin "3") (pinfunction "I_3") (pintype "input"))
      (node (ref "R91") (pin "2") (pinfunction "2_2") (pintype "passive"))
      (node (ref "R95") (pin "2") (pinfunction "2_2") (pintype "passive"))
    )
    (net (code "88") (name "Net-(D21A-O)") (class "Default")
      (node (ref "D21") (pin "2") (pinfunction "O_2") (pintype "output"))
      (node (ref "D21") (pin "5") (pinfunction "I_5") (pintype "input"))
      (node (ref "R94") (pin "2") (pinfunction "2_2") (pintype "passive"))
    )
    (net (code "89") (name "Net-(D21B-O)") (class "Default")
      (node (ref "C34") (pin "2") (pinfunction "2_2") (pintype "passive"))
      (node (ref "D21") (pin "4") (pinfunction "O_4") (pintype "output"))
      (node (ref "R96") (pin "2") (pinfunction "2_2") (pintype "passive"))
    )
    (net (code "90") (name "Net-(D21C-I)") (class "Default")
      (node (ref "C35") (pin "1") (pinfunction "1_1") (pintype "passive"))
      (node (ref "D21") (pin "7") (pinfunction "I_7") (pintype "input"))
      (node (ref "R96") (pin "1") (pinfunction "1_1") (pintype "passive"))
      (node (ref "R97") (pin "1") (pinfunction "1_1") (pintype "passive"))
    )
    (net (code "91") (name "Net-(D21C-O)") (class "Default")
      (node (ref "D21") (pin "6") (pinfunction "O_6") (pintype "output"))
      (node (ref "D21") (pin "9") (pinfunction "I_9") (pintype "input"))
      (node (ref "R98") (pin "B") (pinfunction "B_B") (pintype "passive"))
    )
    (net (code "92") (name "Net-(D21D-O)") (class "Default")
      (node (ref "C35") (pin "2") (pinfunction "2_2") (pintype "passive"))
      (node (ref "D21") (pin "10") (pinfunction "O_10") (pintype "output"))
      (node (ref "D21") (pin "11") (pinfunction "I_11") (pintype "input"))
    )
    (net (code "93") (name "Net-(D21E-O)") (class "Default")
      (node (ref "D21") (pin "12") (pinfunction "O_12") (pintype "output"))
      (node (ref "D21") (pin "14") (pinfunction "I_14") (pintype "input"))
      (node (ref "X9") (pin "2") (pinfunction "2_2") (pintype "passive"))
    )
    (net (code "94") (name "Net-(D21F-O)") (class "Default")
      (node (ref "BQ2") (pin "2") (pinfunction "2_2") (pintype "passive"))
      (node (ref "D21") (pin "15") (pinfunction "O_15") (pintype "output"))
    )
    (net (code "95") (name "Net-(HL3-CATHODE)") (class "Default")
      (node (ref "HL3") (pin "2") (pinfunction "CATHODE_2") (pintype "passive"))
      (node (ref "R27") (pin "2") (pinfunction "2_2") (pintype "passive"))
    )
    (net (code "96") (name "Net-(HL4-CATHODE)") (class "Default")
      (node (ref "HL4") (pin "2") (pinfunction "CATHODE_2") (pintype "passive"))
      (node (ref "R29") (pin "2") (pinfunction "2_2") (pintype "passive"))
    )
    (net (code "97") (name "Net-(HL5-CATHODE)") (class "Default")
      (node (ref "HL5") (pin "2") (pinfunction "CATHODE_2") (pintype "passive"))
      (node (ref "R31") (pin "2") (pinfunction "2_2") (pintype "passive"))
    )
    (net (code "98") (name "Net-(HL6-CATHODE)") (class "Default")
      (node (ref "HL6") (pin "2") (pinfunction "CATHODE_2") (pintype "passive"))
      (node (ref "R33") (pin "2") (pinfunction "2_2") (pintype "passive"))
    )
    (net (code "99") (name "Net-(HL7-CATHODE)") (class "Default")
      (node (ref "HL7") (pin "2") (pinfunction "CATHODE_2") (pintype "passive"))
      (node (ref "R35") (pin "2") (pinfunction "2_2") (pintype "passive"))
    )
    (net (code "100") (name "Net-(HL8-CATHODE)") (class "Default")
      (node (ref "HL8") (pin "2") (pinfunction "CATHODE_2") (pintype "passive"))
      (node (ref "R37") (pin "2") (pinfunction "2_2") (pintype "passive"))
    )
    (net (code "101") (name "Net-(HL9-CATHODE)") (class "Default")
      (node (ref "HL9") (pin "2") (pinfunction "CATHODE_2") (pintype "passive"))
      (node (ref "R39") (pin "2") (pinfunction "2_2") (pintype "passive"))
    )
    (net (code "102") (name "Net-(HL10-CATHODE)") (class "Default")
      (node (ref "HL10") (pin "2") (pinfunction "CATHODE_2") (pintype "passive"))
      (node (ref "R41") (pin "2") (pinfunction "2_2") (pintype "passive"))
    )
    (net (code "103") (name "Net-(HL11-CATHODE)") (class "Default")
      (node (ref "HL11") (pin "2") (pinfunction "CATHODE_2") (pintype "passive"))
      (node (ref "R28") (pin "2") (pinfunction "2_2") (pintype "passive"))
    )
    (net (code "104") (name "Net-(HL12-CATHODE)") (class "Default")
      (node (ref "HL12") (pin "2") (pinfunction "CATHODE_2") (pintype "passive"))
      (node (ref "R30") (pin "2") (pinfunction "2_2") (pintype "passive"))
    )
    (net (code "105") (name "Net-(HL13-CATHODE)") (class "Default")
      (node (ref "HL13") (pin "2") (pinfunction "CATHODE_2") (pintype "passive"))
      (node (ref "R32") (pin "2") (pinfunction "2_2") (pintype "passive"))
    )
    (net (code "106") (name "Net-(HL14-CATHODE)") (class "Default")
      (node (ref "HL14") (pin "2") (pinfunction "CATHODE_2") (pintype "passive"))
      (node (ref "R34") (pin "2") (pinfunction "2_2") (pintype "passive"))
    )
    (net (code "107") (name "Net-(HL15-CATHODE)") (class "Default")
      (node (ref "HL15") (pin "2") (pinfunction "CATHODE_2") (pintype "passive"))
      (node (ref "R36") (pin "2") (pinfunction "2_2") (pintype "passive"))
    )
    (net (code "108") (name "Net-(HL16-CATHODE)") (class "Default")
      (node (ref "HL16") (pin "2") (pinfunction "CATHODE_2") (pintype "passive"))
      (node (ref "R38") (pin "2") (pinfunction "2_2") (pintype "passive"))
    )
    (net (code "109") (name "Net-(HL17-CATHODE)") (class "Default")
      (node (ref "HL17") (pin "2") (pinfunction "CATHODE_2") (pintype "passive"))
      (node (ref "R40") (pin "2") (pinfunction "2_2") (pintype "passive"))
    )
    (net (code "110") (name "Net-(HL18-CATHODE)") (class "Default")
      (node (ref "HL18") (pin "2") (pinfunction "CATHODE_2") (pintype "passive"))
      (node (ref "R42") (pin "2") (pinfunction "2_2") (pintype "passive"))
    )
    (net (code "111") (name "Net-(HL19-CATHODE)") (class "Default")
      (node (ref "HL19") (pin "2") (pinfunction "CATHODE_2") (pintype "passive"))
      (node (ref "R43") (pin "2") (pinfunction "2_2") (pintype "passive"))
    )
    (net (code "112") (name "Net-(HL20-CATHODE)") (class "Default")
      (node (ref "HL20") (pin "2") (pinfunction "CATHODE_2") (pintype "passive"))
      (node (ref "R45") (pin "2") (pinfunction "2_2") (pintype "passive"))
    )
    (net (code "113") (name "Net-(HL21-CATHODE)") (class "Default")
      (node (ref "HL21") (pin "2") (pinfunction "CATHODE_2") (pintype "passive"))
      (node (ref "R47") (pin "2") (pinfunction "2_2") (pintype "passive"))
    )
    (net (code "114") (name "Net-(HL22-CATHODE)") (class "Default")
      (node (ref "HL22") (pin "2") (pinfunction "CATHODE_2") (pintype "passive"))
      (node (ref "R49") (pin "2") (pinfunction "2_2") (pintype "passive"))
    )
    (net (code "115") (name "Net-(HL23-CATHODE)") (class "Default")
      (node (ref "HL23") (pin "2") (pinfunction "CATHODE_2") (pintype "passive"))
      (node (ref "R51") (pin "2") (pinfunction "2_2") (pintype "passive"))
    )
    (net (code "116") (name "Net-(HL24-CATHODE)") (class "Default")
      (node (ref "HL24") (pin "2") (pinfunction "CATHODE_2") (pintype "passive"))
      (node (ref "R53") (pin "2") (pinfunction "2_2") (pintype "passive"))
    )
    (net (code "117") (name "Net-(HL25-CATHODE)") (class "Default")
      (node (ref "HL25") (pin "2") (pinfunction "CATHODE_2") (pintype "passive"))
      (node (ref "R55") (pin "2") (pinfunction "2_2") (pintype "passive"))
    )
    (net (code "118") (name "Net-(HL26-CATHODE)") (class "Default")
      (node (ref "HL26") (pin "2") (pinfunction "CATHODE_2") (pintype "passive"))
      (node (ref "R57") (pin "2") (pinfunction "2_2") (pintype "passive"))
    )
    (net (code "119") (name "Net-(HL27-CATHODE)") (class "Default")
      (node (ref "HL27") (pin "2") (pinfunction "CATHODE_2") (pintype "passive"))
      (node (ref "R44") (pin "2") (pinfunction "2_2") (pintype "passive"))
    )
    (net (code "120") (name "Net-(HL28-CATHODE)") (class "Default")
      (node (ref "HL28") (pin "2") (pinfunction "CATHODE_2") (pintype "passive"))
      (node (ref "R46") (pin "2") (pinfunction "2_2") (pintype "passive"))
    )
    (net (code "121") (name "Net-(HL29-CATHODE)") (class "Default")
      (node (ref "HL29") (pin "2") (pinfunction "CATHODE_2") (pintype "passive"))
      (node (ref "R48") (pin "2") (pinfunction "2_2") (pintype "passive"))
    )
    (net (code "122") (name "Net-(HL30-CATHODE)") (class "Default")
      (node (ref "HL30") (pin "2") (pinfunction "CATHODE_2") (pintype "passive"))
      (node (ref "R50") (pin "2") (pinfunction "2_2") (pintype "passive"))
    )
    (net (code "123") (name "Net-(HL31-CATHODE)") (class "Default")
      (node (ref "HL31") (pin "2") (pinfunction "CATHODE_2") (pintype "passive"))
      (node (ref "R52") (pin "2") (pinfunction "2_2") (pintype "passive"))
    )
    (net (code "124") (name "Net-(HL32-CATHODE)") (class "Default")
      (node (ref "HL32") (pin "2") (pinfunction "CATHODE_2") (pintype "passive"))
      (node (ref "R54") (pin "2") (pinfunction "2_2") (pintype "passive"))
    )
    (net (code "125") (name "Net-(HL33-CATHODE)") (class "Default")
      (node (ref "HL33") (pin "2") (pinfunction "CATHODE_2") (pintype "passive"))
      (node (ref "R56") (pin "2") (pinfunction "2_2") (pintype "passive"))
    )
    (net (code "126") (name "Net-(HL34-CATHODE)") (class "Default")
      (node (ref "HL34") (pin "2") (pinfunction "CATHODE_2") (pintype "passive"))
      (node (ref "R58") (pin "2") (pinfunction "2_2") (pintype "passive"))
    )
    (net (code "127") (name "Net-(HL35-CATHODE)") (class "Default")
      (node (ref "HL35") (pin "2") (pinfunction "CATHODE_2") (pintype "passive"))
      (node (ref "R59") (pin "2") (pinfunction "2_2") (pintype "passive"))
    )
    (net (code "128") (name "Net-(HL36-CATHODE)") (class "Default")
      (node (ref "HL36") (pin "2") (pinfunction "CATHODE_2") (pintype "passive"))
      (node (ref "R61") (pin "2") (pinfunction "2_2") (pintype "passive"))
    )
    (net (code "129") (name "Net-(HL37-CATHODE)") (class "Default")
      (node (ref "HL37") (pin "2") (pinfunction "CATHODE_2") (pintype "passive"))
      (node (ref "R63") (pin "2") (pinfunction "2_2") (pintype "passive"))
    )
    (net (code "130") (name "Net-(HL38-CATHODE)") (class "Default")
      (node (ref "HL38") (pin "2") (pinfunction "CATHODE_2") (pintype "passive"))
      (node (ref "R65") (pin "2") (pinfunction "2_2") (pintype "passive"))
    )
    (net (code "131") (name "Net-(HL39-CATHODE)") (class "Default")
      (node (ref "HL39") (pin "2") (pinfunction "CATHODE_2") (pintype "passive"))
      (node (ref "R67") (pin "2") (pinfunction "2_2") (pintype "passive"))
    )
    (net (code "132") (name "Net-(HL40-CATHODE)") (class "Default")
      (node (ref "HL40") (pin "2") (pinfunction "CATHODE_2") (pintype "passive"))
      (node (ref "R69") (pin "2") (pinfunction "2_2") (pintype "passive"))
    )
    (net (code "133") (name "Net-(HL41-CATHODE)") (class "Default")
      (node (ref "HL41") (pin "2") (pinfunction "CATHODE_2") (pintype "passive"))
      (node (ref "R71") (pin "2") (pinfunction "2_2") (pintype "passive"))
    )
    (net (code "134") (name "Net-(HL42-CATHODE)") (class "Default")
      (node (ref "HL42") (pin "2") (pinfunction "CATHODE_2") (pintype "passive"))
      (node (ref "R73") (pin "2") (pinfunction "2_2") (pintype "passive"))
    )
    (net (code "135") (name "Net-(HL43-CATHODE)") (class "Default")
      (node (ref "HL43") (pin "2") (pinfunction "CATHODE_2") (pintype "passive"))
      (node (ref "R60") (pin "2") (pinfunction "2_2") (pintype "passive"))
    )
    (net (code "136") (name "Net-(HL44-CATHODE)") (class "Default")
      (node (ref "HL44") (pin "2") (pinfunction "CATHODE_2") (pintype "passive"))
      (node (ref "R62") (pin "2") (pinfunction "2_2") (pintype "passive"))
    )
    (net (code "137") (name "Net-(HL45-CATHODE)") (class "Default")
      (node (ref "HL45") (pin "2") (pinfunction "CATHODE_2") (pintype "passive"))
      (node (ref "R64") (pin "2") (pinfunction "2_2") (pintype "passive"))
    )
    (net (code "138") (name "Net-(HL46-CATHODE)") (class "Default")
      (node (ref "HL46") (pin "2") (pinfunction "CATHODE_2") (pintype "passive"))
      (node (ref "R66") (pin "2") (pinfunction "2_2") (pintype "passive"))
    )
    (net (code "139") (name "Net-(HL47-CATHODE)") (class "Default")
      (node (ref "HL47") (pin "2") (pinfunction "CATHODE_2") (pintype "passive"))
      (node (ref "R68") (pin "2") (pinfunction "2_2") (pintype "passive"))
    )
    (net (code "140") (name "Net-(HL48-CATHODE)") (class "Default")
      (node (ref "HL48") (pin "2") (pinfunction "CATHODE_2") (pintype "passive"))
      (node (ref "R70") (pin "2") (pinfunction "2_2") (pintype "passive"))
    )
    (net (code "141") (name "Net-(HL49-CATHODE)") (class "Default")
      (node (ref "HL49") (pin "2") (pinfunction "CATHODE_2") (pintype "passive"))
      (node (ref "R72") (pin "2") (pinfunction "2_2") (pintype "passive"))
    )
    (net (code "142") (name "Net-(HL50-CATHODE)") (class "Default")
      (node (ref "HL50") (pin "2") (pinfunction "CATHODE_2") (pintype "passive"))
      (node (ref "R74") (pin "2") (pinfunction "2_2") (pintype "passive"))
    )
    (net (code "143") (name "Net-(HL51-CATHODE)") (class "Default")
      (node (ref "HL51") (pin "2") (pinfunction "CATHODE_2") (pintype "passive"))
      (node (ref "R75") (pin "2") (pinfunction "2_2") (pintype "passive"))
    )
    (net (code "144") (name "Net-(HL52-CATHODE)") (class "Default")
      (node (ref "HL52") (pin "2") (pinfunction "CATHODE_2") (pintype "passive"))
      (node (ref "R77") (pin "2") (pinfunction "2_2") (pintype "passive"))
    )
    (net (code "145") (name "Net-(HL53-CATHODE)") (class "Default")
      (node (ref "HL53") (pin "2") (pinfunction "CATHODE_2") (pintype "passive"))
      (node (ref "R79") (pin "2") (pinfunction "2_2") (pintype "passive"))
    )
    (net (code "146") (name "Net-(HL54-CATHODE)") (class "Default")
      (node (ref "HL54") (pin "2") (pinfunction "CATHODE_2") (pintype "passive"))
      (node (ref "R81") (pin "2") (pinfunction "2_2") (pintype "passive"))
    )
    (net (code "147") (name "Net-(HL55-CATHODE)") (class "Default")
      (node (ref "HL55") (pin "2") (pinfunction "CATHODE_2") (pintype "passive"))
      (node (ref "R83") (pin "2") (pinfunction "2_2") (pintype "passive"))
    )
    (net (code "148") (name "Net-(HL56-CATHODE)") (class "Default")
      (node (ref "HL56") (pin "2") (pinfunction "CATHODE_2") (pintype "passive"))
      (node (ref "R85") (pin "2") (pinfunction "2_2") (pintype "passive"))
    )
    (net (code "149") (name "Net-(HL57-CATHODE)") (class "Default")
      (node (ref "HL57") (pin "2") (pinfunction "CATHODE_2") (pintype "passive"))
      (node (ref "R87") (pin "2") (pinfunction "2_2") (pintype "passive"))
    )
    (net (code "150") (name "Net-(HL58-CATHODE)") (class "Default")
      (node (ref "HL58") (pin "2") (pinfunction "CATHODE_2") (pintype "passive"))
      (node (ref "R89") (pin "2") (pinfunction "2_2") (pintype "passive"))
    )
    (net (code "151") (name "Net-(HL59-CATHODE)") (class "Default")
      (node (ref "HL59") (pin "2") (pinfunction "CATHODE_2") (pintype "passive"))
      (node (ref "R76") (pin "2") (pinfunction "2_2") (pintype "passive"))
    )
    (net (code "152") (name "Net-(HL60-CATHODE)") (class "Default")
      (node (ref "HL60") (pin "2") (pinfunction "CATHODE_2") (pintype "passive"))
      (node (ref "R78") (pin "2") (pinfunction "2_2") (pintype "passive"))
    )
    (net (code "153") (name "Net-(HL61-CATHODE)") (class "Default")
      (node (ref "HL61") (pin "2") (pinfunction "CATHODE_2") (pintype "passive"))
      (node (ref "R80") (pin "2") (pinfunction "2_2") (pintype "passive"))
    )
    (net (code "154") (name "Net-(HL62-CATHODE)") (class "Default")
      (node (ref "HL62") (pin "2") (pinfunction "CATHODE_2") (pintype "passive"))
      (node (ref "R82") (pin "2") (pinfunction "2_2") (pintype "passive"))
    )
    (net (code "155") (name "Net-(HL63-CATHODE)") (class "Default")
      (node (ref "HL63") (pin "2") (pinfunction "CATHODE_2") (pintype "passive"))
      (node (ref "R84") (pin "2") (pinfunction "2_2") (pintype "passive"))
    )
    (net (code "156") (name "Net-(HL64-CATHODE)") (class "Default")
      (node (ref "HL64") (pin "2") (pinfunction "CATHODE_2") (pintype "passive"))
      (node (ref "R86") (pin "2") (pinfunction "2_2") (pintype "passive"))
    )
    (net (code "157") (name "Net-(HL65-CATHODE)") (class "Default")
      (node (ref "HL65") (pin "2") (pinfunction "CATHODE_2") (pintype "passive"))
      (node (ref "R88") (pin "2") (pinfunction "2_2") (pintype "passive"))
    )
    (net (code "158") (name "Net-(HL66-CATHODE)") (class "Default")
      (node (ref "HL66") (pin "2") (pinfunction "CATHODE_2") (pintype "passive"))
      (node (ref "R90") (pin "2") (pinfunction "2_2") (pintype "passive"))
    )
    (net (code "159") (name "Net-(R97-Pad2)") (class "Default")
      (node (ref "R97") (pin "2") (pinfunction "2_2") (pintype "passive"))
      (node (ref "R98") (pin "A") (pinfunction "A_A") (pintype "passive"))
      (node (ref "R98") (pin "WIPER") (pinfunction "WIPER_WIPER") (pintype "passive"))
    )
    (net (code "160") (name "Net-(VT1-BASE)") (class "Default")
      (node (ref "R92") (pin "2") (pinfunction "2_2") (pintype "passive"))
      (node (ref "R93") (pin "1") (pinfunction "1_1") (pintype "passive"))
      (node (ref "VT1") (pin "1") (pinfunction "BASE_1") (pintype "input"))
    )
    (net (code "161") (name "Net-(VT1-COLLECTOR)") (class "Default")
      (node (ref "R91") (pin "1") (pinfunction "1_1") (pintype "passive"))
      (node (ref "VT1") (pin "3") (pinfunction "COLLECTOR_3") (pintype "passive"))
    )
    (net (code "162") (name "Net-(VT2-BASE)") (class "Default")
      (node (ref "R100") (pin "1") (pinfunction "1_1") (pintype "passive"))
      (node (ref "R99") (pin "2") (pinfunction "2_2") (pintype "passive"))
      (node (ref "VT2") (pin "1") (pinfunction "BASE_1") (pintype "input"))
    )
    (net (code "163") (name "Net-(VT2-COLLECTOR)") (class "Default")
      (node (ref "C36") (pin "1") (pinfunction "1_1") (pintype "passive"))
      (node (ref "VT2") (pin "3") (pinfunction "COLLECTOR_3") (pintype "passive"))
    )
    (net (code "164") (name "VCC") (class "Default")
      (node (ref "D12") (pin "14") (pinfunction "VCC_14") (pintype "power_in"))
      (node (ref "D13") (pin "20") (pinfunction "VCC_20") (pintype "power_in"))
      (node (ref "D14") (pin "20") (pinfunction "VCC_20") (pintype "power_in"))
      (node (ref "D15") (pin "20") (pinfunction "VCC_20") (pintype "power_in"))
      (node (ref "D16") (pin "20") (pinfunction "VCC_20") (pintype "power_in"))
      (node (ref "D17") (pin "20") (pinfunction "VCC_20") (pintype "power_in"))
      (node (ref "D18") (pin "20") (pinfunction "VCC_20") (pintype "power_in"))
      (node (ref "D19") (pin "20") (pinfunction "VCC_20") (pintype "power_in"))
      (node (ref "D20") (pin "20") (pinfunction "VCC_20") (pintype "power_in"))
      (node (ref "D4") (pin "VCC") (pinfunction "VCC_VCC") (pintype "power_in"))
    )
    (net (code "165") (name "WR0") (class "Default")
      (node (ref "D4") (pin "11") (pinfunction "I_11") (pintype "input"))
    )
    (net (code "166") (name "WR1") (class "Default")
      (node (ref "D12") (pin "5") (pinfunction "A_5") (pintype "input"))
    )
    (net (code "167") (name "WR2") (class "Default")
      (node (ref "D4") (pin "13") (pinfunction "I_13") (pintype "input"))
    )
    (net (code "168") (name "WR3") (class "Default")
      (node (ref "D12") (pin "9") (pinfunction "A_9") (pintype "input"))
    )
    (net (code "169") (name "WR4") (class "Default")
      (node (ref "D12") (pin "1") (pinfunction "A_1") (pintype "input"))
    )
    (net (code "170") (name "WR5") (class "Default")
      (node (ref "D12") (pin "11") (pinfunction "A_11") (pintype "input"))
    )
    (net (code "171") (name "WR6") (class "Default")
      (node (ref "D12") (pin "3") (pinfunction "A_3") (pintype "input"))
    )
    (net (code "172") (name "WR7") (class "Default")
      (node (ref "D12") (pin "13") (pinfunction "A_13") (pintype "input"))
    )
  )
)
